# MCU.net
KiCad netlist of a schematic drawn in Altium Designer
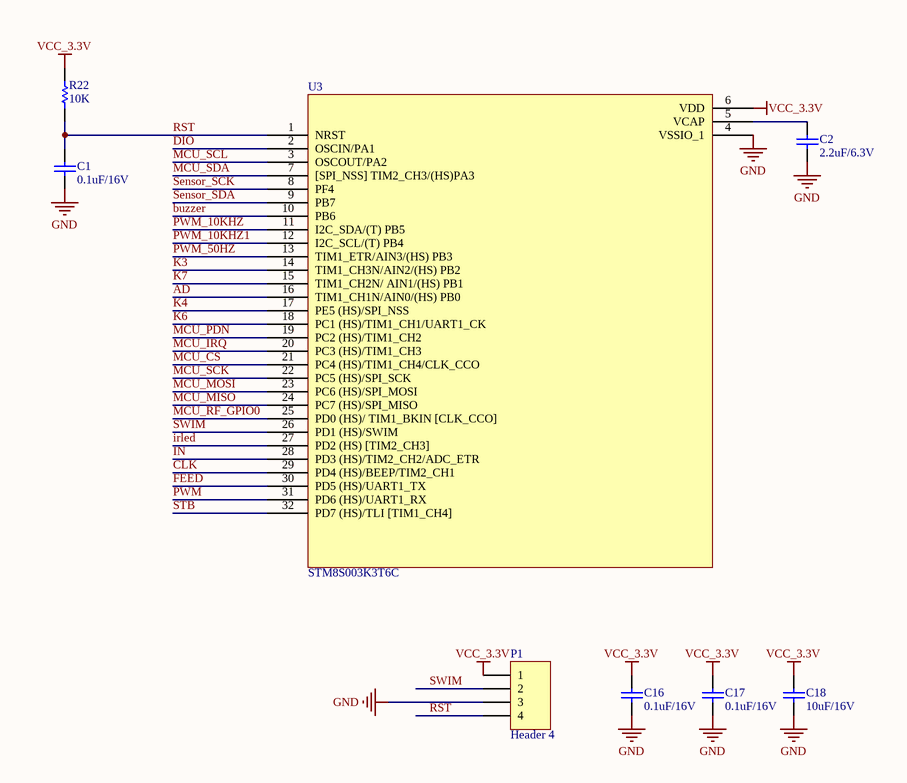
[diagram p0: MCU.SchDoc]

(export (version "E")
  (design (tool "Eeschema 10.0.6"))
  (components
    (comp (ref "C1")
      (value "0.1uF/16V")
      (footprint "0603C")
      (description "Capacitor")
      (fields (field (name "PUBLISHER") "Altium Limited"))
      (libsource (lib "Miscellaneous Devices") (part "Cap"))
    )
    (comp (ref "C2")
      (value "2.2uF/6.3V")
      (footprint "0603C")
      (description "Capacitor")
      (fields (field (name "PUBLISHER") "Altium Limited"))
      (libsource (lib "Miscellaneous Devices") (part "Cap"))
    )
    (comp (ref "C16")
      (value "0.1uF/16V")
      (footprint "0603C")
      (description "Capacitor")
      (fields (field (name "PUBLISHER") "Altium Limited"))
      (libsource (lib "Miscellaneous Devices") (part "Cap"))
    )
    (comp (ref "C17")
      (value "0.1uF/16V")
      (footprint "0603C")
      (description "Capacitor")
      (fields (field (name "PUBLISHER") "Altium Limited"))
      (libsource (lib "Miscellaneous Devices") (part "Cap"))
    )
    (comp (ref "C18")
      (value "10uF/16V")
      (footprint "0603C")
      (description "Capacitor")
      (fields (field (name "PUBLISHER") "Altium Limited"))
      (libsource (lib "Miscellaneous Devices") (part "Cap"))
    )
    (comp (ref "P1")
      (value "Header 4")
      (footprint "HDR1X4")
      (description "Header, 4-Pin")
      (fields (field (name "PUBLISHER") "Altium Limited"))
      (libsource (lib "Miscellaneous Connectors") (part "Header 4"))
    )
    (comp (ref "R22")
      (value "10K")
      (footprint "0603R")
      (description "Resistor")
      (fields (field (name "PUBLISHER") "Altium Limited"))
      (libsource (lib "Miscellaneous Devices") (part "Res1"))
    )
    (comp (ref "U3")
      (value "STM8S003K3T6C")
      (footprint "QFP80P900X900X245-32N")
      (libsource (lib "Schlib_20110825") (part "STM8S003K3T6C"))
    )
  )
  (nets
    (net (code "1") (name "/AD") (class "Default")
      (node (ref "U3") (pin "16") (pinfunction "TIM1_CH1N/AIN0/(HS)_PB0_16") (pintype "passive"))
    )
    (net (code "2") (name "/CLK") (class "Default")
      (node (ref "U3") (pin "29") (pinfunction "PD4_(HS)/BEEP/TIM2_CH1_29") (pintype "passive"))
    )
    (net (code "3") (name "/DIO") (class "Default")
      (node (ref "U3") (pin "2") (pinfunction "OSCIN/PA1_2") (pintype "passive"))
    )
    (net (code "4") (name "/FEED") (class "Default")
      (node (ref "U3") (pin "30") (pinfunction "PD5_(HS)/UART1_TX_30") (pintype "passive"))
    )
    (net (code "5") (name "/IN") (class "Default")
      (node (ref "U3") (pin "28") (pinfunction "PD3_(HS)/TIM2_CH2/ADC_ETR_28") (pintype "passive"))
    )
    (net (code "6") (name "/K3") (class "Default")
      (node (ref "U3") (pin "14") (pinfunction "TIM1_CH3N/AIN2/(HS)_PB2_14") (pintype "passive"))
    )
    (net (code "7") (name "/K4") (class "Default")
      (node (ref "U3") (pin "17") (pinfunction "PE5_(HS)/SPI_NSS_17") (pintype "passive"))
    )
    (net (code "8") (name "/K6") (class "Default")
      (node (ref "U3") (pin "18") (pinfunction "PC1_(HS)/TIM1_CH1/UART1_CK_18") (pintype "passive"))
    )
    (net (code "9") (name "/K7") (class "Default")
      (node (ref "U3") (pin "15") (pinfunction "TIM1_CH2N/_AIN1/(HS)_PB1_15") (pintype "passive"))
    )
    (net (code "10") (name "/MCU_CS") (class "Default")
      (node (ref "U3") (pin "21") (pinfunction "PC4_(HS)/TIM1_CH4/CLK_CCO_21") (pintype "passive"))
    )
    (net (code "11") (name "/MCU_IRQ") (class "Default")
      (node (ref "U3") (pin "20") (pinfunction "PC3_(HS)/TIM1_CH3_20") (pintype "passive"))
    )
    (net (code "12") (name "/MCU_MISO") (class "Default")
      (node (ref "U3") (pin "24") (pinfunction "PC7_(HS)/SPI_MISO_24") (pintype "passive"))
    )
    (net (code "13") (name "/MCU_MOSI") (class "Default")
      (node (ref "U3") (pin "23") (pinfunction "PC6_(HS)/SPI_MOSI_23") (pintype "passive"))
    )
    (net (code "14") (name "/MCU_PDN") (class "Default")
      (node (ref "U3") (pin "19") (pinfunction "PC2_(HS)/TIM1_CH2_19") (pintype "passive"))
    )
    (net (code "15") (name "/MCU_RF_GPIO0") (class "Default")
      (node (ref "U3") (pin "25") (pinfunction "PD0_(HS)/_TIM1_BKIN_[CLK_CCO]_25") (pintype "passive"))
    )
    (net (code "16") (name "/MCU_SCK") (class "Default")
      (node (ref "U3") (pin "22") (pinfunction "PC5_(HS)/SPI_SCK_22") (pintype "passive"))
    )
    (net (code "17") (name "/MCU_SCL") (class "Default")
      (node (ref "U3") (pin "3") (pinfunction "OSCOUT/PA2_3") (pintype "passive"))
    )
    (net (code "18") (name "/MCU_SDA") (class "Default")
      (node (ref "U3") (pin "7") (pinfunction "[SPI_NSS]_TIM2_CH3/(HS)PA3_7") (pintype "passive"))
    )
    (net (code "19") (name "/PWM") (class "Default")
      (node (ref "U3") (pin "31") (pinfunction "PD6_(HS)/UART1_RX_31") (pintype "passive"))
    )
    (net (code "20") (name "/PWM_10KHZ") (class "Default")
      (node (ref "U3") (pin "11") (pinfunction "I2C_SDA/(T)_PB5_11") (pintype "passive"))
    )
    (net (code "21") (name "/PWM_10KHZ1") (class "Default")
      (node (ref "U3") (pin "12") (pinfunction "I2C_SCL/(T)_PB4_12") (pintype "passive"))
    )
    (net (code "22") (name "/PWM_50HZ") (class "Default")
      (node (ref "U3") (pin "13") (pinfunction "TIM1_ETR/AIN3/(HS)_PB3_13") (pintype "passive"))
    )
    (net (code "23") (name "/RST") (class "Default")
      (node (ref "C1") (pin "1") (pinfunction "1_1") (pintype "passive"))
      (node (ref "P1") (pin "4") (pinfunction "4_4") (pintype "passive"))
      (node (ref "R22") (pin "1") (pinfunction "1_1") (pintype "passive"))
      (node (ref "U3") (pin "1") (pinfunction "NRST_1") (pintype "passive"))
    )
    (net (code "24") (name "/STB") (class "Default")
      (node (ref "U3") (pin "32") (pinfunction "PD7_(HS)/TLI_[TIM1_CH4]_32") (pintype "passive"))
    )
    (net (code "25") (name "/SWIM") (class "Default")
      (node (ref "P1") (pin "2") (pinfunction "2_2") (pintype "passive"))
      (node (ref "U3") (pin "26") (pinfunction "PD1_(HS)/SWIM_26") (pintype "passive"))
    )
    (net (code "26") (name "/Sensor_SCK") (class "Default")
      (node (ref "U3") (pin "8") (pinfunction "PF4_8") (pintype "passive"))
    )
    (net (code "27") (name "/Sensor_SDA") (class "Default")
      (node (ref "U3") (pin "9") (pinfunction "PB7_9") (pintype "passive"))
    )
    (net (code "28") (name "/buzzer") (class "Default")
      (node (ref "U3") (pin "10") (pinfunction "PB6_10") (pintype "passive"))
    )
    (net (code "29") (name "/irled") (class "Default")
      (node (ref "U3") (pin "27") (pinfunction "PD2_(HS)_[TIM2_CH3]_27") (pintype "passive"))
    )
    (net (code "30") (name "GND") (class "Default")
      (node (ref "C1") (pin "2") (pinfunction "2_2") (pintype "passive"))
      (node (ref "C16") (pin "2") (pinfunction "2_2") (pintype "passive"))
      (node (ref "C17") (pin "2") (pinfunction "2_2") (pintype "passive"))
      (node (ref "C18") (pin "2") (pinfunction "2_2") (pintype "passive"))
      (node (ref "C2") (pin "1") (pinfunction "1_1") (pintype "passive"))
      (node (ref "P1") (pin "3") (pinfunction "3_3") (pintype "passive"))
      (node (ref "U3") (pin "4") (pinfunction "VSSIO_1_4") (pintype "passive"))
    )
    (net (code "31") (name "Net-(U3-VCAP)") (class "Default")
      (node (ref "C2") (pin "2") (pinfunction "2_2") (pintype "passive"))
      (node (ref "U3") (pin "5") (pinfunction "VCAP_5") (pintype "passive"))
    )
    (net (code "32") (name "VCC_3.3V") (class "Default")
      (node (ref "C16") (pin "1") (pinfunction "1_1") (pintype "passive"))
      (node (ref "C17") (pin "1") (pinfunction "1_1") (pintype "passive"))
      (node (ref "C18") (pin "1") (pinfunction "1_1") (pintype "passive"))
      (node (ref "P1") (pin "1") (pinfunction "1_1") (pintype "passive"))
      (node (ref "R22") (pin "2") (pinfunction "2_2") (pintype "passive"))
      (node (ref "U3") (pin "6") (pinfunction "VDD_6") (pintype "passive"))
    )
  )
)
